# SCH_V1.net
KiCad netlist of a schematic drawn in Altium Designer
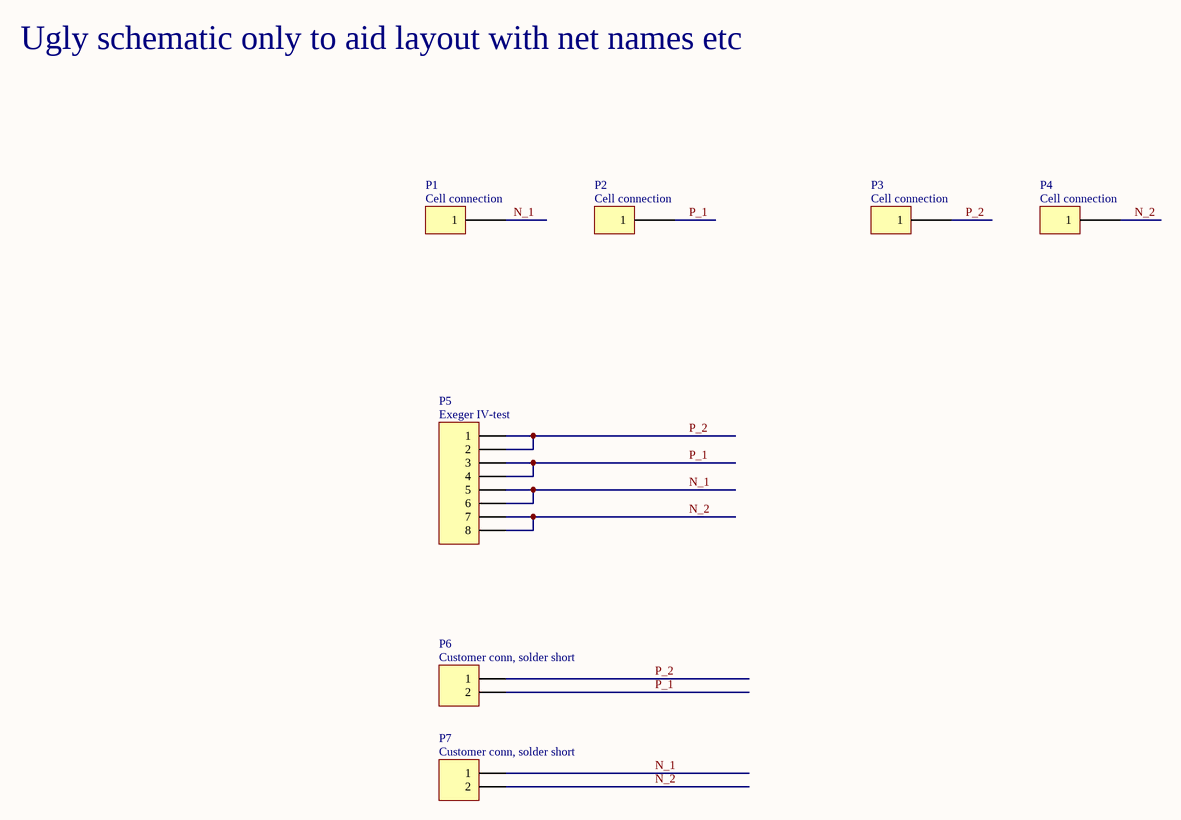
[diagram p0: SCH_V1.SchDoc]

(export (version "E")
  (design (tool "Eeschema 10.0.6"))
  (components
    (comp (ref "P1")
      (value "Cell connection")
      (footprint "Cell_pad_2.5mm")
      (libsource (lib "Flex_SCH_symbols") (part "Cell connection 1P"))
    )
    (comp (ref "P2")
      (value "Cell connection")
      (footprint "Cell_pad_2.5mm")
      (libsource (lib "Flex_SCH_symbols") (part "Cell connection 1P"))
    )
    (comp (ref "P3")
      (value "Cell connection")
      (footprint "Cell_pad_2.5mm")
      (libsource (lib "Flex_SCH_symbols") (part "Cell connection 1P"))
    )
    (comp (ref "P4")
      (value "Cell connection")
      (footprint "Cell_pad_2.5mm")
      (libsource (lib "Flex_SCH_symbols") (part "Cell connection 1P"))
    )
    (comp (ref "P5")
      (value "Exeger IV-test")
      (footprint "EXEGER_IV_8_PIN_NO_STIFF")
      (description "Header, 8-Pin")
      (libsource (lib "Miscellaneous Connectors") (part "Header 8"))
    )
    (comp (ref "P6")
      (value "Customer conn, solder short")
      (footprint "Customer_2022_solder_short")
      (description "Header, 2-Pin")
      (libsource (lib "Miscellaneous Connectors") (part "Header 2"))
    )
    (comp (ref "P7")
      (value "Customer conn, solder short")
      (footprint "Customer_2022_solder_short")
      (description "Header, 2-Pin")
      (libsource (lib "Miscellaneous Connectors") (part "Header 2"))
    )
  )
  (nets
    (net (code "1") (name "/N_1") (class "Default")
      (node (ref "P1") (pin "1") (pinfunction "1_1") (pintype "passive"))
      (node (ref "P5") (pin "5") (pinfunction "5_5") (pintype "passive"))
      (node (ref "P5") (pin "6") (pinfunction "6_6") (pintype "passive"))
      (node (ref "P7") (pin "1") (pinfunction "1_1") (pintype "passive"))
    )
    (net (code "2") (name "/N_2") (class "Default")
      (node (ref "P4") (pin "1") (pinfunction "1_1") (pintype "passive"))
      (node (ref "P5") (pin "7") (pinfunction "7_7") (pintype "passive"))
      (node (ref "P5") (pin "8") (pinfunction "8_8") (pintype "passive"))
      (node (ref "P7") (pin "2") (pinfunction "2_2") (pintype "passive"))
    )
    (net (code "3") (name "/P_1") (class "Default")
      (node (ref "P2") (pin "1") (pinfunction "1_1") (pintype "passive"))
      (node (ref "P5") (pin "3") (pinfunction "3_3") (pintype "passive"))
      (node (ref "P5") (pin "4") (pinfunction "4_4") (pintype "passive"))
      (node (ref "P6") (pin "2") (pinfunction "2_2") (pintype "passive"))
    )
    (net (code "4") (name "/P_2") (class "Default")
      (node (ref "P3") (pin "1") (pinfunction "1_1") (pintype "passive"))
      (node (ref "P5") (pin "1") (pinfunction "1_1") (pintype "passive"))
      (node (ref "P5") (pin "2") (pinfunction "2_2") (pintype "passive"))
      (node (ref "P6") (pin "1") (pinfunction "1_1") (pintype "passive"))
    )
  )
)
